# Son_of_Dark_Power.net
KiCad netlist of a schematic drawn in EAGLE
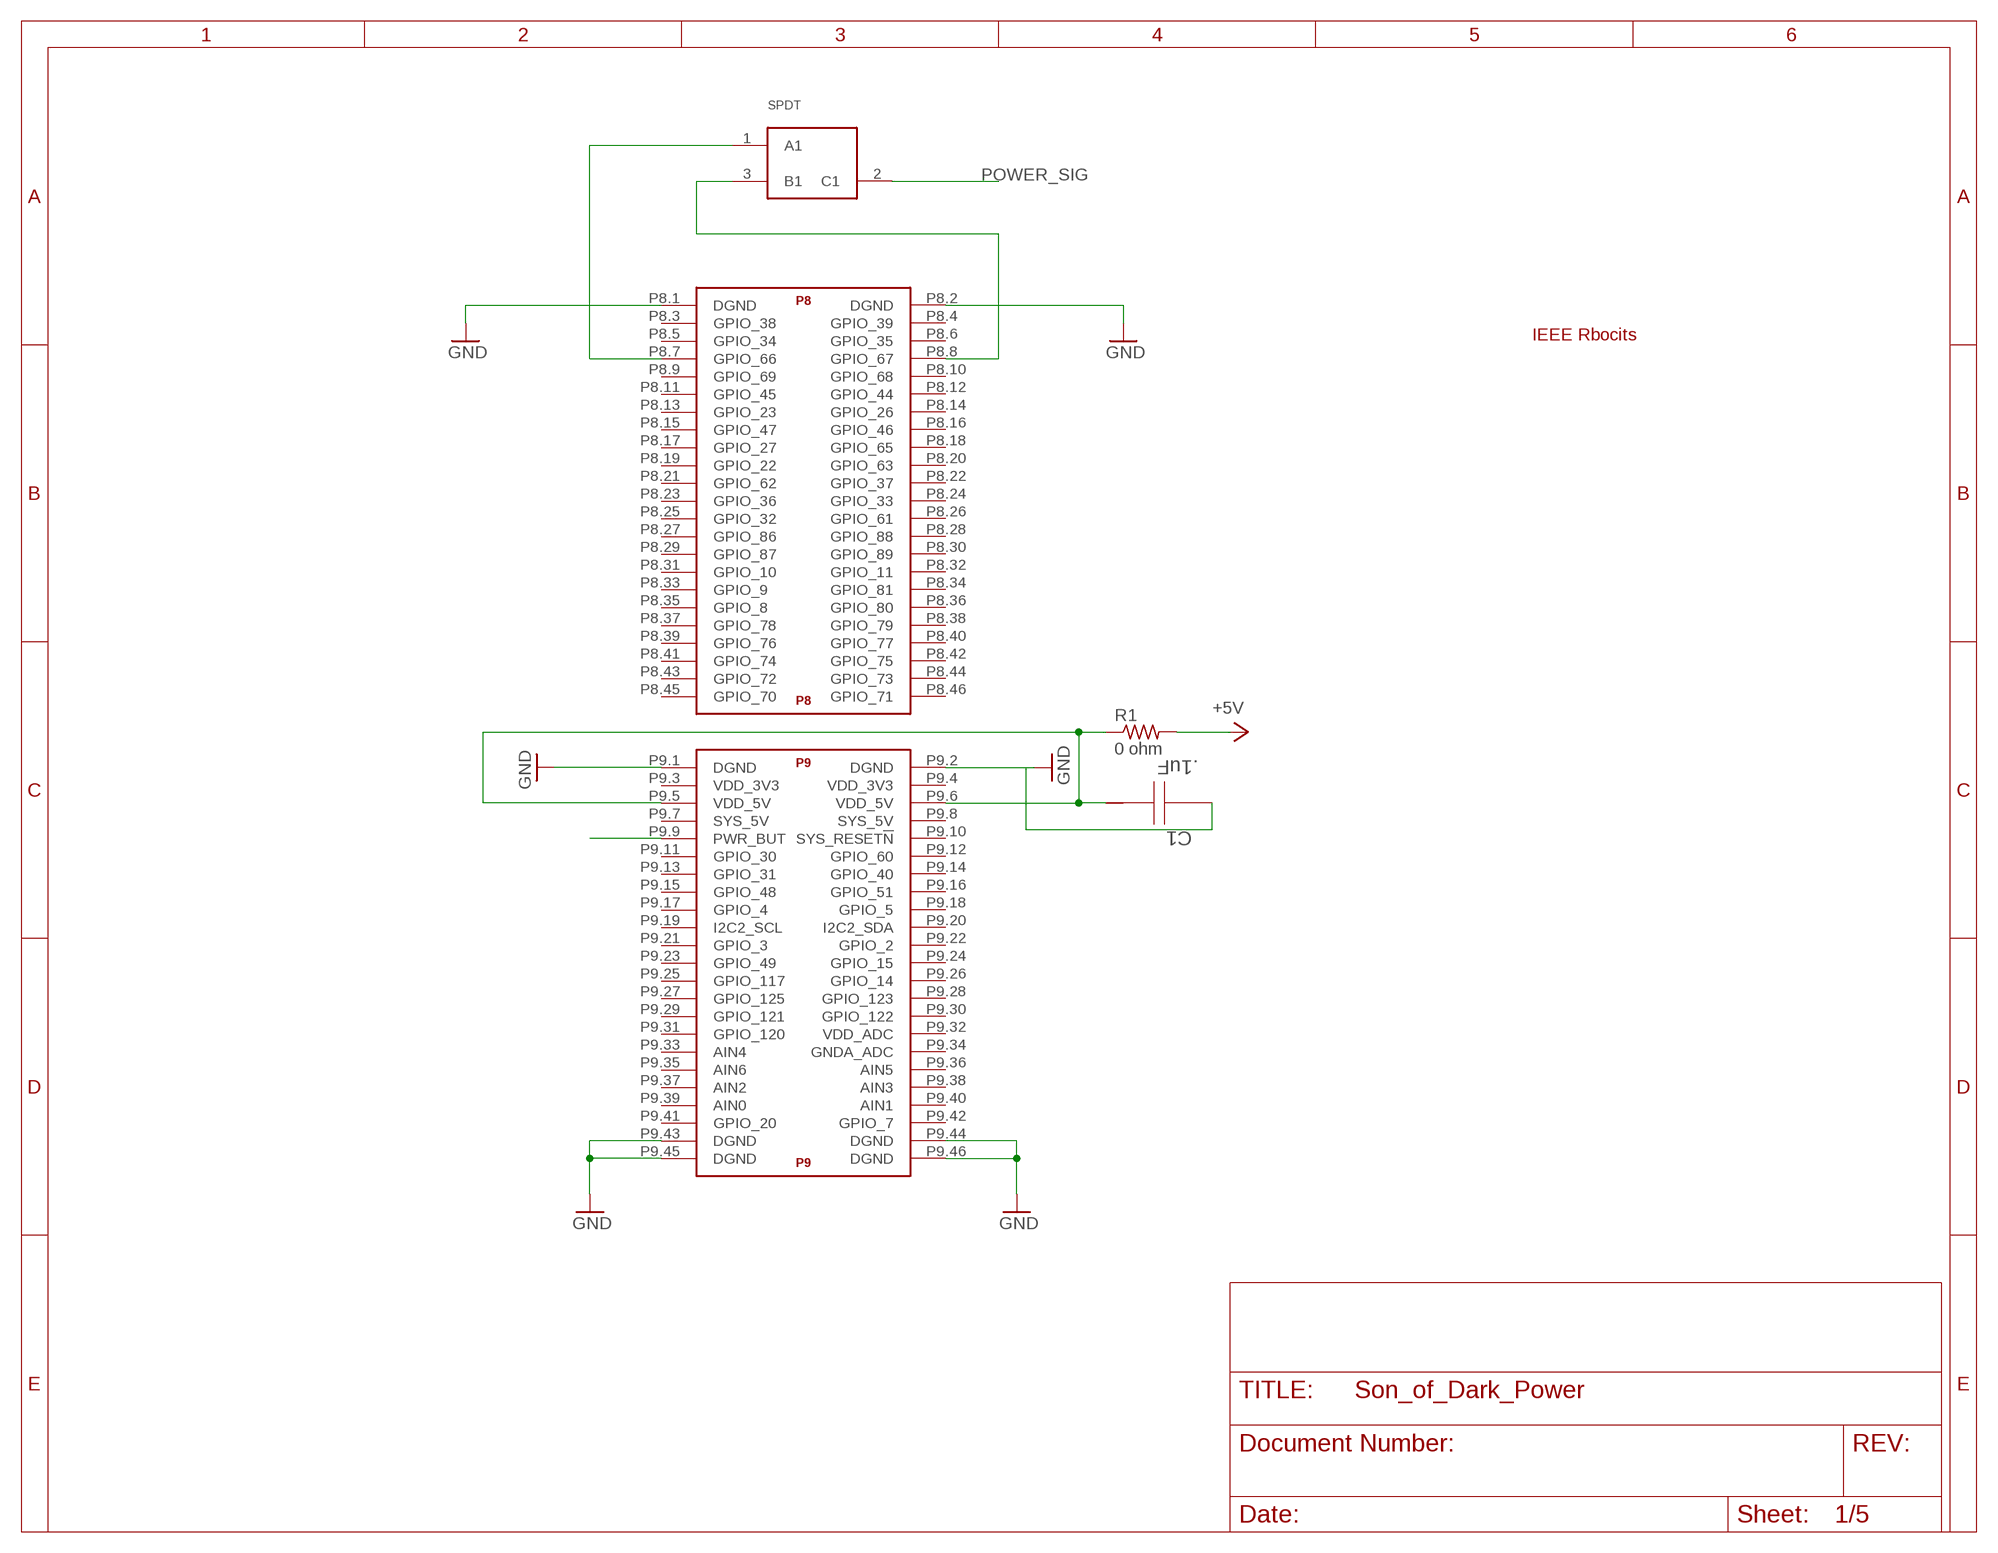
[diagram p0: schematic, sheet 1]
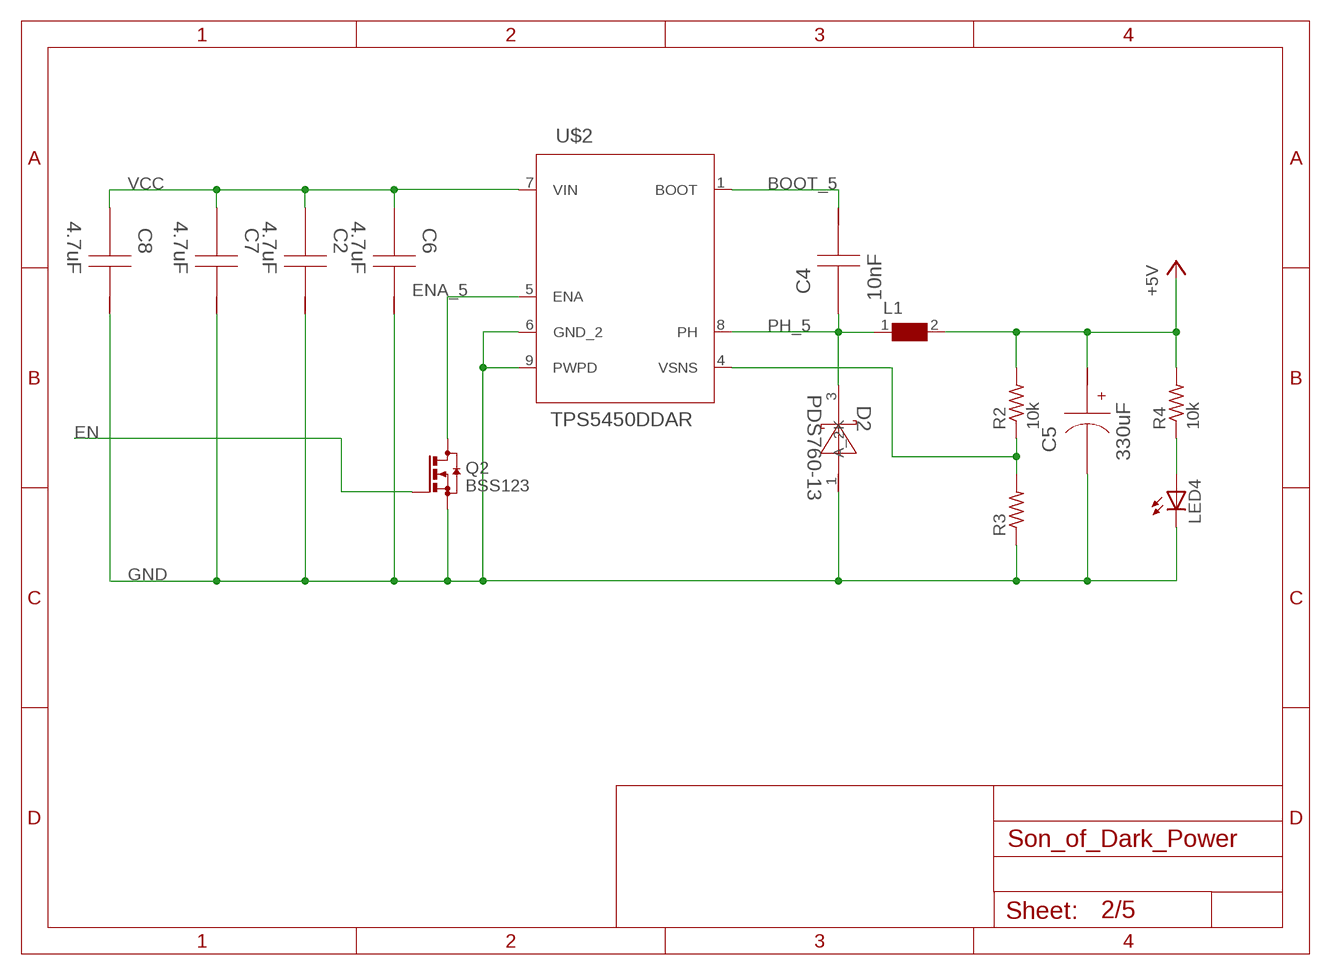
[diagram p1: schematic, sheet 2]
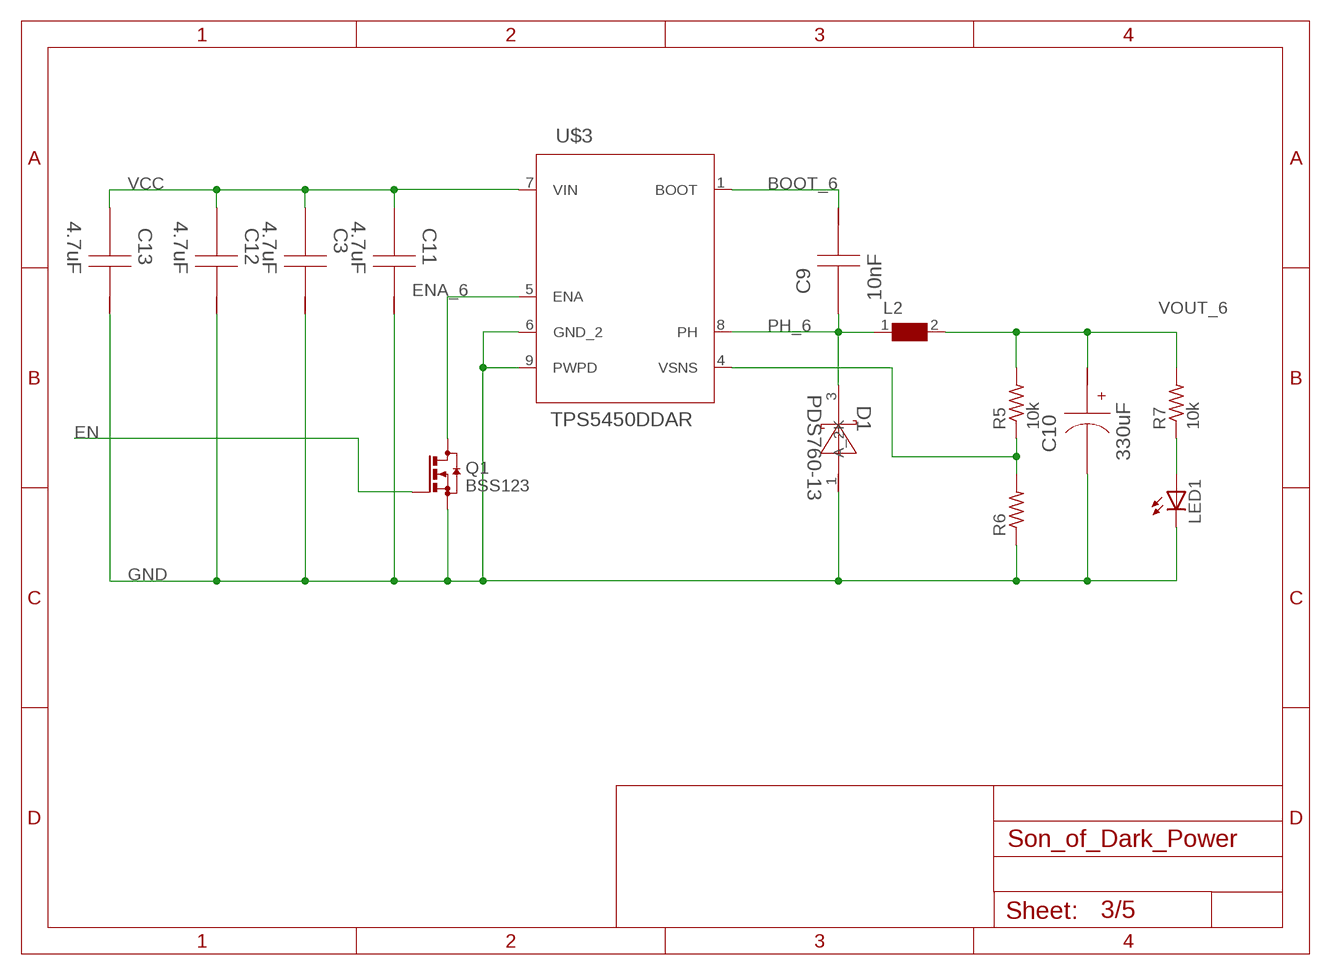
[diagram p2: schematic, sheet 3]
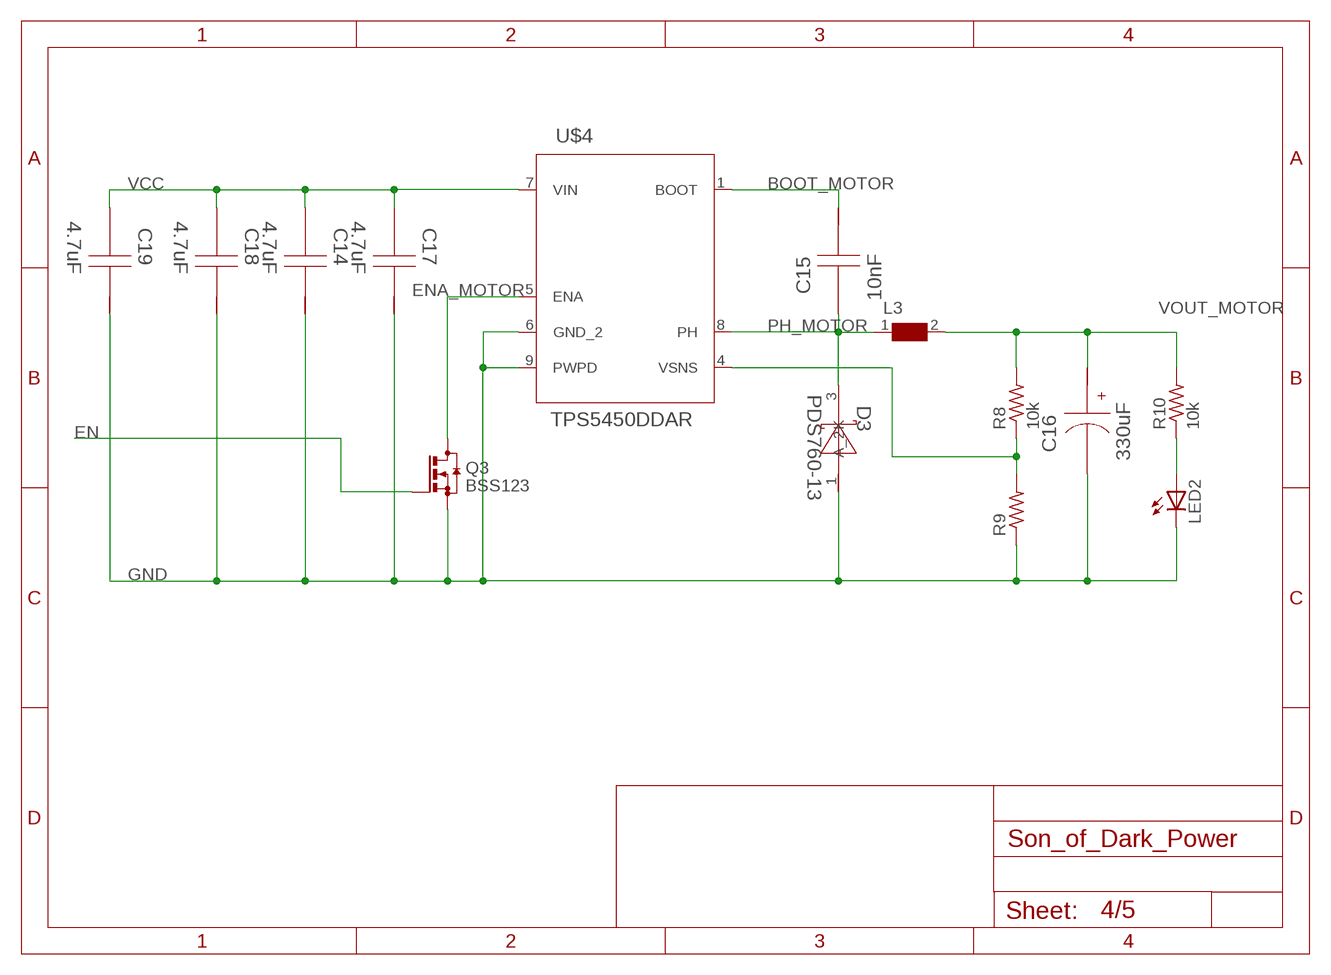
[diagram p3: schematic, sheet 4]
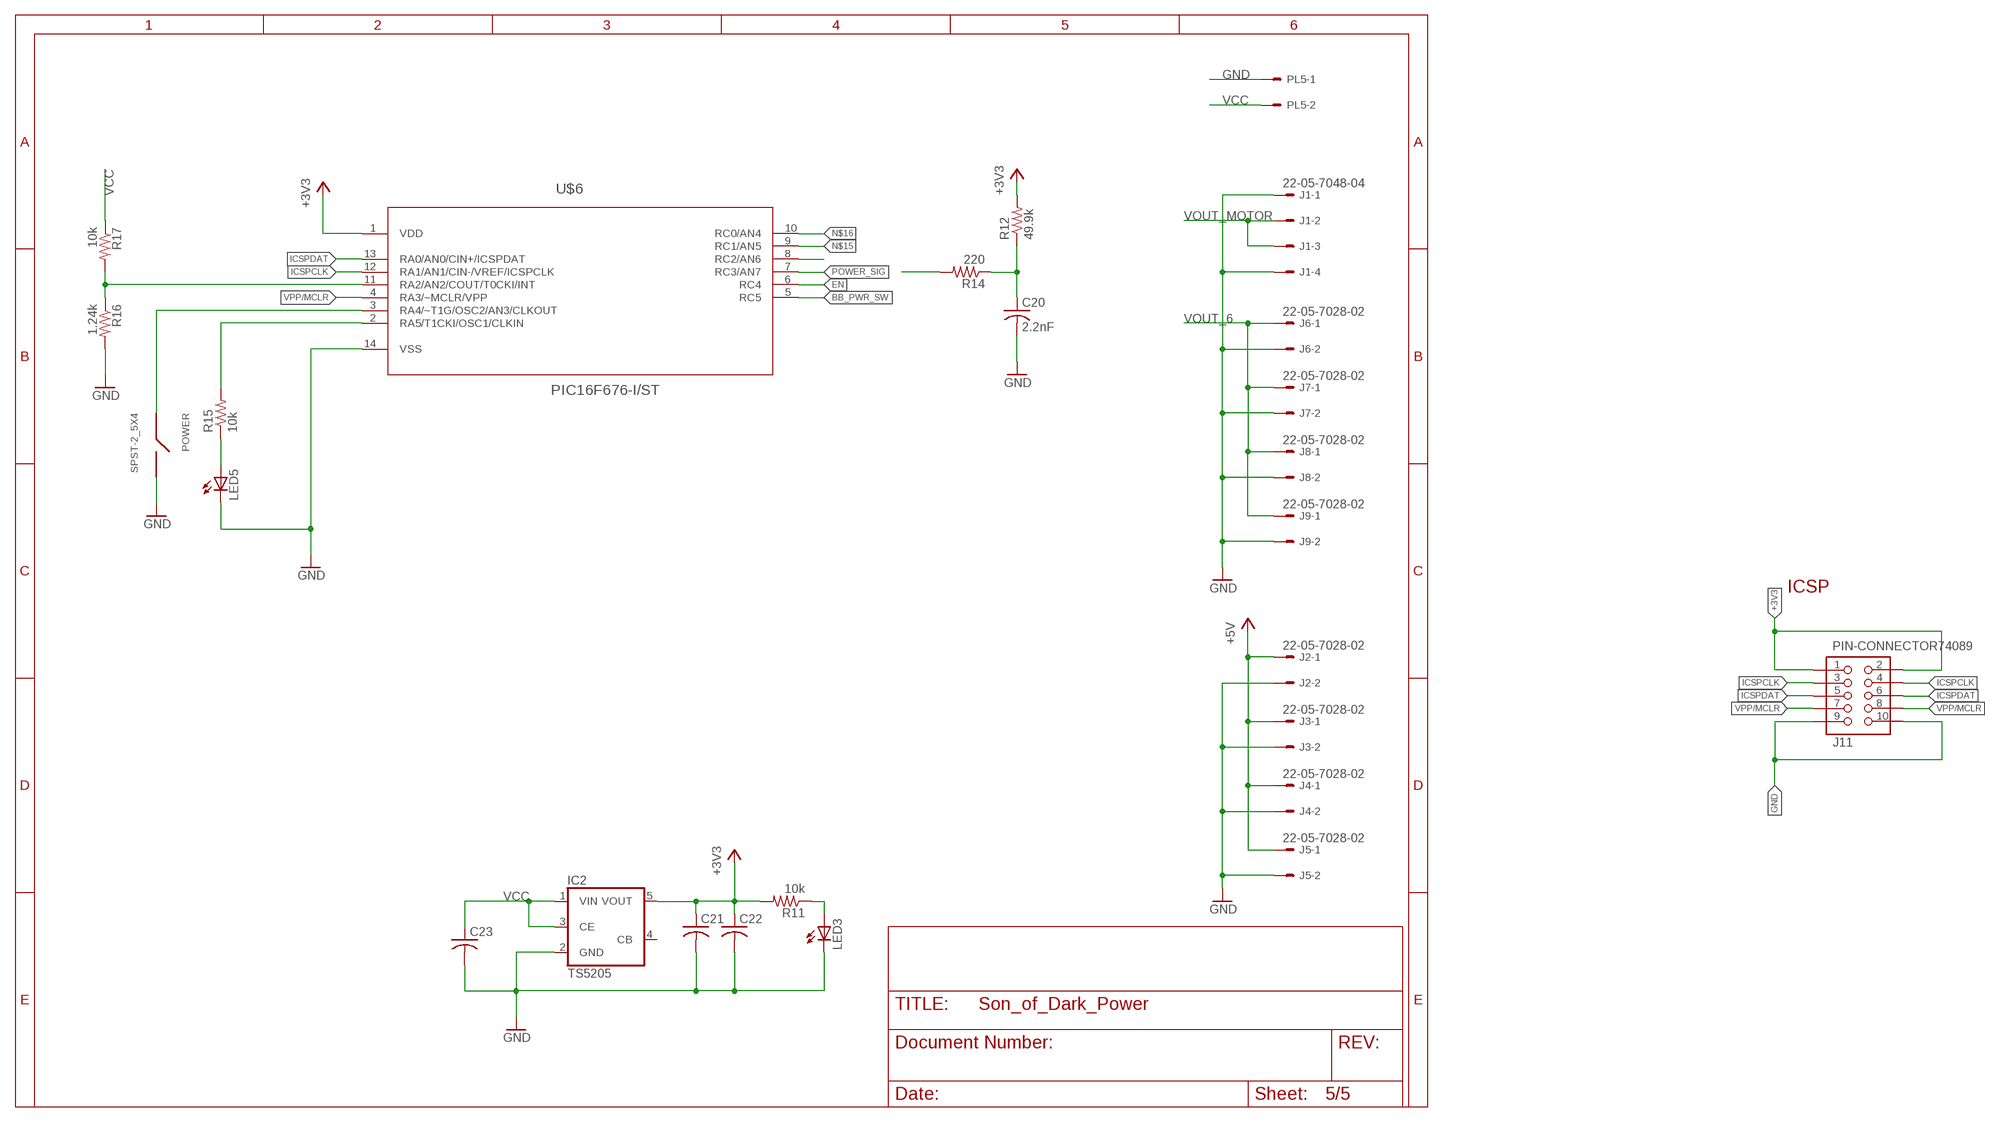
[diagram p4: schematic, sheet 5]

(export (version "E")
  (design (tool "Eeschema 10.0.6"))
  (components
    (comp (ref "C14")
      (value "4.7uF")
      (footprint "eagle-import:1206")
      (fields (field (name "MANUFACTURER_PART_NUMBER") "GRM31CR71H475KA12L"))
      (libsource (lib "eagle-import") (part "GRM31CR71H475KA12L"))
    )
    (comp (ref "C15")
      (value "10nF")
      (footprint "eagle-import:0805")
      (fields (field (name "MANUFACTURER_PART_NUMBER") "C0805C103K5RACTU"))
      (libsource (lib "eagle-import") (part "C0805C103K5RACTU"))
    )
    (comp (ref "C16")
      (value "330uF")
      (footprint "eagle-import:SM_RADIAL_10AMM")
      (fields (field (name "MANUFACTURER_PART_NUMBER") "10SVP330MX"))
      (libsource (lib "eagle-import") (part "10SVP330MX"))
    )
    (comp (ref "C17")
      (value "4.7uF")
      (footprint "eagle-import:1206")
      (fields (field (name "MANUFACTURER_PART_NUMBER") "GRM31CR71H475KA12L"))
      (libsource (lib "eagle-import") (part "GRM31CR71H475KA12L"))
    )
    (comp (ref "C18")
      (value "4.7uF")
      (footprint "eagle-import:1206")
      (fields (field (name "MANUFACTURER_PART_NUMBER") "GRM31CR71H475KA12L"))
      (libsource (lib "eagle-import") (part "GRM31CR71H475KA12L"))
    )
    (comp (ref "C19")
      (value "4.7uF")
      (footprint "eagle-import:1206")
      (fields (field (name "MANUFACTURER_PART_NUMBER") "GRM31CR71H475KA12L"))
      (libsource (lib "eagle-import") (part "GRM31CR71H475KA12L"))
    )
    (comp (ref "D3")
      (value "PDS760-13")
      (footprint "eagle-import:POWERDI5")
      (libsource (lib "eagle-import") (part "PDS760-13"))
    )
    (comp (ref "L3")
      (value "WE-HCC-7443331000_1090")
      (footprint "eagle-import:WE-HCC_1090")
      (fields (field (name "MPN") "7443331000"))
      (libsource (lib "eagle-import") (part "WE-HCC_1090-7443331000"))
    )
    (comp (ref "LED2")
      (value "LEDSML1206")
      (footprint "eagle-import:SML1206")
      (libsource (lib "eagle-import") (part "LEDSML1206"))
    )
    (comp (ref "Q3")
      (value "BSS123")
      (footprint "eagle-import:SOT23")
      (libsource (lib "eagle-import") (part "BSS123"))
    )
    (comp (ref "R8")
      (value "10k")
      (footprint "eagle-import:R1206")
      (libsource (lib "eagle-import") (part "R-US_R1206"))
    )
    (comp (ref "R9")
      (value "R-US_R1206")
      (footprint "eagle-import:R1206")
      (libsource (lib "eagle-import") (part "R-US_R1206"))
    )
    (comp (ref "R10")
      (value "10k")
      (footprint "eagle-import:R1206")
      (libsource (lib "eagle-import") (part "R-US_R1206"))
    )
    (comp (ref "U$4")
      (value "TPS5450DDAR")
      (footprint "eagle-import:R-PDSO-G8")
      (fields (field (name "MANUFACTURER_PART_NUMBER") "TPS5450DDA"))
      (libsource (lib "eagle-import") (part "TPS5450DDAR"))
    )
    (comp (ref "C20")
      (value "2.2nF")
      (footprint "eagle-import:C0603")
      (libsource (lib "eagle-import") (part "C-USC0603"))
    )
    (comp (ref "C21")
      (value "C-USC0603")
      (footprint "eagle-import:C0603")
      (libsource (lib "eagle-import") (part "C-USC0603"))
    )
    (comp (ref "C22")
      (value "C-USC0603")
      (footprint "eagle-import:C0603")
      (libsource (lib "eagle-import") (part "C-USC0603"))
    )
    (comp (ref "C23")
      (value "C-USC0603")
      (footprint "eagle-import:C0603")
      (libsource (lib "eagle-import") (part "C-USC0603"))
    )
    (comp (ref "IC2")
      (value "TS5205")
      (footprint "eagle-import:SOT25")
      (libsource (lib "eagle-import") (part "TS5205"))
    )
    (comp (ref "J1")
      (value "22-05-7048-04")
      (footprint "eagle-import:7395-04")
      (libsource (lib "eagle-import") (part "22-?-0405-7048"))
    )
    (comp (ref "J2")
      (value "22-05-7028-02")
      (footprint "eagle-import:7395-02")
      (libsource (lib "eagle-import") (part "22-?-0205-7028"))
    )
    (comp (ref "J3")
      (value "22-05-7028-02")
      (footprint "eagle-import:7395-02")
      (libsource (lib "eagle-import") (part "22-?-0205-7028"))
    )
    (comp (ref "J4")
      (value "22-05-7028-02")
      (footprint "eagle-import:7395-02")
      (libsource (lib "eagle-import") (part "22-?-0205-7028"))
    )
    (comp (ref "J5")
      (value "22-05-7028-02")
      (footprint "eagle-import:7395-02")
      (libsource (lib "eagle-import") (part "22-?-0205-7028"))
    )
    (comp (ref "J6")
      (value "22-05-7028-02")
      (footprint "eagle-import:7395-02")
      (libsource (lib "eagle-import") (part "22-?-0205-7028"))
    )
    (comp (ref "J7")
      (value "22-05-7028-02")
      (footprint "eagle-import:7395-02")
      (libsource (lib "eagle-import") (part "22-?-0205-7028"))
    )
    (comp (ref "J8")
      (value "22-05-7028-02")
      (footprint "eagle-import:7395-02")
      (libsource (lib "eagle-import") (part "22-?-0205-7028"))
    )
    (comp (ref "J9")
      (value "22-05-7028-02")
      (footprint "eagle-import:7395-02")
      (libsource (lib "eagle-import") (part "22-?-0205-7028"))
    )
    (comp (ref "J11")
      (value "PIN-CONNECTOR74089")
      (footprint "eagle-import:10-PIN-SMD")
      (libsource (lib "eagle-import") (part "PIN-CONNECTOR74089"))
    )
    (comp (ref "LED3")
      (value "LEDSML1206")
      (footprint "eagle-import:SML1206")
      (libsource (lib "eagle-import") (part "LEDSML1206"))
    )
    (comp (ref "LED5")
      (value "LEDSML1206")
      (footprint "eagle-import:SML1206")
      (libsource (lib "eagle-import") (part "LEDSML1206"))
    )
    (comp (ref "PL5")
      (value "555X-2H")
      (footprint "eagle-import:5569-2")
      (libsource (lib "eagle-import") (part "555X-2H"))
    )
    (comp (ref "POWER")
      (value "SPST-2_5X4")
      (footprint "eagle-import:SPST-TAC-4X2_5MM")
      (libsource (lib "eagle-import") (part "SPST-2_5X4"))
    )
    (comp (ref "R11")
      (value "10k")
      (footprint "eagle-import:R1206")
      (libsource (lib "eagle-import") (part "R-US_R1206"))
    )
    (comp (ref "R12")
      (value "49.9k")
      (footprint "eagle-import:R0603")
      (libsource (lib "eagle-import") (part "R-US_R0603"))
    )
    (comp (ref "R14")
      (value "220")
      (footprint "eagle-import:R0603")
      (libsource (lib "eagle-import") (part "R-US_R0603"))
    )
    (comp (ref "R15")
      (value "10k")
      (footprint "eagle-import:R1206")
      (libsource (lib "eagle-import") (part "R-US_R1206"))
    )
    (comp (ref "R16")
      (value "1.24k")
      (footprint "eagle-import:R0603")
      (libsource (lib "eagle-import") (part "R-US_R0603"))
    )
    (comp (ref "R17")
      (value "10k")
      (footprint "eagle-import:R0603")
      (libsource (lib "eagle-import") (part "R-US_R0603"))
    )
    (comp (ref "U$6")
      (value "PIC16F676-I/ST")
      (footprint "eagle-import:SOP65P640X120-14N")
      (libsource (lib "eagle-import") (part "PIC16F676-I/ST"))
    )
    (comp (ref "C1")
      (value ".1uF")
      (footprint "eagle-import:1206")
      (fields (field (name "MANUFACTURER_PART_NUMBER") "C3216X5R1A106K"))
      (libsource (lib "eagle-import") (part "C3216X5R1A106K"))
    )
    (comp (ref "R1")
      (value "0 ohm")
      (footprint "eagle-import:R1206")
      (libsource (lib "eagle-import") (part "R-US_R1206"))
    )
    (comp (ref "SPDT")
      (value "SPDT_SWITCH")
      (footprint "eagle-import:SPDT")
      (libsource (lib "eagle-import") (part "SPDT_SWITCH"))
    )
    (comp (ref "U$1")
      (value "BEAGLE_BONE_BLACK_CAPE")
      (footprint "eagle-import:BEAGLE_BONE_BLACK_CAPE")
      (libsource (lib "eagle-import") (part "BEAGLE_BONE_BLACK_CAPE"))
    )
    (comp (ref "U$5")
      (value "LOGO-IEEE")
      (footprint "eagle-import:LOGO")
      (libsource (lib "eagle-import") (part "LOGO-IEEE"))
    )
    (comp (ref "C3")
      (value "4.7uF")
      (footprint "eagle-import:1206")
      (fields (field (name "MANUFACTURER_PART_NUMBER") "GRM31CR71H475KA12L"))
      (libsource (lib "eagle-import") (part "GRM31CR71H475KA12L"))
    )
    (comp (ref "C9")
      (value "10nF")
      (footprint "eagle-import:0805")
      (fields (field (name "MANUFACTURER_PART_NUMBER") "C0805C103K5RACTU"))
      (libsource (lib "eagle-import") (part "C0805C103K5RACTU"))
    )
    (comp (ref "C10")
      (value "330uF")
      (footprint "eagle-import:SM_RADIAL_10AMM")
      (fields (field (name "MANUFACTURER_PART_NUMBER") "10SVP330MX"))
      (libsource (lib "eagle-import") (part "10SVP330MX"))
    )
    (comp (ref "C11")
      (value "4.7uF")
      (footprint "eagle-import:1206")
      (fields (field (name "MANUFACTURER_PART_NUMBER") "GRM31CR71H475KA12L"))
      (libsource (lib "eagle-import") (part "GRM31CR71H475KA12L"))
    )
    (comp (ref "C12")
      (value "4.7uF")
      (footprint "eagle-import:1206")
      (fields (field (name "MANUFACTURER_PART_NUMBER") "GRM31CR71H475KA12L"))
      (libsource (lib "eagle-import") (part "GRM31CR71H475KA12L"))
    )
    (comp (ref "C13")
      (value "4.7uF")
      (footprint "eagle-import:1206")
      (fields (field (name "MANUFACTURER_PART_NUMBER") "GRM31CR71H475KA12L"))
      (libsource (lib "eagle-import") (part "GRM31CR71H475KA12L"))
    )
    (comp (ref "D1")
      (value "PDS760-13")
      (footprint "eagle-import:POWERDI5")
      (libsource (lib "eagle-import") (part "PDS760-13"))
    )
    (comp (ref "L2")
      (value "WE-HCC-7443331000_1090")
      (footprint "eagle-import:WE-HCC_1090")
      (fields (field (name "MPN") "7443331000"))
      (libsource (lib "eagle-import") (part "WE-HCC_1090-7443331000"))
    )
    (comp (ref "LED1")
      (value "LEDSML1206")
      (footprint "eagle-import:SML1206")
      (libsource (lib "eagle-import") (part "LEDSML1206"))
    )
    (comp (ref "Q1")
      (value "BSS123")
      (footprint "eagle-import:SOT23")
      (libsource (lib "eagle-import") (part "BSS123"))
    )
    (comp (ref "R5")
      (value "10k")
      (footprint "eagle-import:R1206")
      (libsource (lib "eagle-import") (part "R-US_R1206"))
    )
    (comp (ref "R6")
      (value "R-US_R1206")
      (footprint "eagle-import:R1206")
      (libsource (lib "eagle-import") (part "R-US_R1206"))
    )
    (comp (ref "R7")
      (value "10k")
      (footprint "eagle-import:R1206")
      (libsource (lib "eagle-import") (part "R-US_R1206"))
    )
    (comp (ref "U$3")
      (value "TPS5450DDAR")
      (footprint "eagle-import:R-PDSO-G8")
      (fields (field (name "MANUFACTURER_PART_NUMBER") "TPS5450DDA"))
      (libsource (lib "eagle-import") (part "TPS5450DDAR"))
    )
    (comp (ref "C2")
      (value "4.7uF")
      (footprint "eagle-import:1206")
      (fields (field (name "MANUFACTURER_PART_NUMBER") "GRM31CR71H475KA12L"))
      (libsource (lib "eagle-import") (part "GRM31CR71H475KA12L"))
    )
    (comp (ref "C4")
      (value "10nF")
      (footprint "eagle-import:0805")
      (fields (field (name "MANUFACTURER_PART_NUMBER") "C0805C103K5RACTU"))
      (libsource (lib "eagle-import") (part "C0805C103K5RACTU"))
    )
    (comp (ref "C5")
      (value "330uF")
      (footprint "eagle-import:SM_RADIAL_10AMM")
      (fields (field (name "MANUFACTURER_PART_NUMBER") "10SVP330MX"))
      (libsource (lib "eagle-import") (part "10SVP330MX"))
    )
    (comp (ref "C6")
      (value "4.7uF")
      (footprint "eagle-import:1206")
      (fields (field (name "MANUFACTURER_PART_NUMBER") "GRM31CR71H475KA12L"))
      (libsource (lib "eagle-import") (part "GRM31CR71H475KA12L"))
    )
    (comp (ref "C7")
      (value "4.7uF")
      (footprint "eagle-import:1206")
      (fields (field (name "MANUFACTURER_PART_NUMBER") "GRM31CR71H475KA12L"))
      (libsource (lib "eagle-import") (part "GRM31CR71H475KA12L"))
    )
    (comp (ref "C8")
      (value "4.7uF")
      (footprint "eagle-import:1206")
      (fields (field (name "MANUFACTURER_PART_NUMBER") "GRM31CR71H475KA12L"))
      (libsource (lib "eagle-import") (part "GRM31CR71H475KA12L"))
    )
    (comp (ref "D2")
      (value "PDS760-13")
      (footprint "eagle-import:POWERDI5")
      (libsource (lib "eagle-import") (part "PDS760-13"))
    )
    (comp (ref "L1")
      (value "WE-HCC-7443331000_1090")
      (footprint "eagle-import:WE-HCC_1090")
      (fields (field (name "MPN") "7443331000"))
      (libsource (lib "eagle-import") (part "WE-HCC_1090-7443331000"))
    )
    (comp (ref "LED4")
      (value "LEDSML1206")
      (footprint "eagle-import:SML1206")
      (libsource (lib "eagle-import") (part "LEDSML1206"))
    )
    (comp (ref "Q2")
      (value "BSS123")
      (footprint "eagle-import:SOT23")
      (libsource (lib "eagle-import") (part "BSS123"))
    )
    (comp (ref "R2")
      (value "10k")
      (footprint "eagle-import:R1206")
      (libsource (lib "eagle-import") (part "R-US_R1206"))
    )
    (comp (ref "R3")
      (value "R-US_R1206")
      (footprint "eagle-import:R1206")
      (libsource (lib "eagle-import") (part "R-US_R1206"))
    )
    (comp (ref "R4")
      (value "10k")
      (footprint "eagle-import:R1206")
      (libsource (lib "eagle-import") (part "R-US_R1206"))
    )
    (comp (ref "U$2")
      (value "TPS5450DDAR")
      (footprint "eagle-import:R-PDSO-G8")
      (fields (field (name "MANUFACTURER_PART_NUMBER") "TPS5450DDA"))
      (libsource (lib "eagle-import") (part "TPS5450DDAR"))
    )
  )
  (nets
    (net (code "1") (name "+3V3") (class "Default")
      (node (ref "C21") (pin "1") (pinfunction "1_1") (pintype "passive"))
      (node (ref "C22") (pin "1") (pinfunction "1_1") (pintype "passive"))
      (node (ref "IC2") (pin "5") (pinfunction "VOUT_5") (pintype "passive"))
      (node (ref "J11") (pin "1") (pinfunction "P$1_1") (pintype "power_in"))
      (node (ref "J11") (pin "2") (pinfunction "P$2_2") (pintype "power_in"))
      (node (ref "R11") (pin "2") (pinfunction "2_2") (pintype "passive"))
      (node (ref "R12") (pin "2") (pinfunction "2_2") (pintype "passive"))
      (node (ref "U$6") (pin "1") (pinfunction "VDD_1") (pintype "power_in"))
    )
    (net (code "2") (name "+5V") (class "Default")
      (node (ref "C5") (pin "1") (pinfunction "+_1") (pintype "passive"))
      (node (ref "J2") (pin "1") (pinfunction "S_1") (pintype "passive"))
      (node (ref "J3") (pin "1") (pinfunction "S_1") (pintype "passive"))
      (node (ref "J4") (pin "1") (pinfunction "S_1") (pintype "passive"))
      (node (ref "J5") (pin "1") (pinfunction "S_1") (pintype "passive"))
      (node (ref "L1") (pin "2") (pinfunction "2_2") (pintype "passive"))
      (node (ref "R1") (pin "2") (pinfunction "2_2") (pintype "passive"))
      (node (ref "R2") (pin "2") (pinfunction "2_2") (pintype "passive"))
      (node (ref "R4") (pin "2") (pinfunction "2_2") (pintype "passive"))
    )
    (net (code "3") (name "BB_PWR_SW") (class "Default")
      (node (ref "U$1") (pin "P9.9") (pinfunction "PWR_BUT_P9.9") (pintype "bidirectional"))
      (node (ref "U$6") (pin "5") (pinfunction "RC5_5") (pintype "bidirectional"))
    )
    (net (code "4") (name "BOOT_5") (class "Default")
      (node (ref "C4") (pin "1") (pinfunction "1_1") (pintype "passive"))
      (node (ref "U$2") (pin "1") (pinfunction "BOOT_1") (pintype "passive"))
    )
    (net (code "5") (name "BOOT_6") (class "Default")
      (node (ref "C9") (pin "1") (pinfunction "1_1") (pintype "passive"))
      (node (ref "U$3") (pin "1") (pinfunction "BOOT_1") (pintype "passive"))
    )
    (net (code "6") (name "BOOT_MOTOR") (class "Default")
      (node (ref "C15") (pin "1") (pinfunction "1_1") (pintype "passive"))
      (node (ref "U$4") (pin "1") (pinfunction "BOOT_1") (pintype "passive"))
    )
    (net (code "7") (name "EN") (class "Default")
      (node (ref "Q1") (pin "1") (pinfunction "G_1") (pintype "passive"))
      (node (ref "Q2") (pin "1") (pinfunction "G_1") (pintype "passive"))
      (node (ref "Q3") (pin "1") (pinfunction "G_1") (pintype "passive"))
      (node (ref "U$6") (pin "6") (pinfunction "RC4_6") (pintype "bidirectional"))
    )
    (net (code "8") (name "ENA_5") (class "Default")
      (node (ref "Q2") (pin "3") (pinfunction "D_3") (pintype "passive"))
      (node (ref "U$2") (pin "5") (pinfunction "ENA_5") (pintype "passive"))
    )
    (net (code "9") (name "ENA_6") (class "Default")
      (node (ref "Q1") (pin "3") (pinfunction "D_3") (pintype "passive"))
      (node (ref "U$3") (pin "5") (pinfunction "ENA_5") (pintype "passive"))
    )
    (net (code "10") (name "ENA_MOTOR") (class "Default")
      (node (ref "Q3") (pin "3") (pinfunction "D_3") (pintype "passive"))
      (node (ref "U$4") (pin "5") (pinfunction "ENA_5") (pintype "passive"))
    )
    (net (code "11") (name "GND") (class "Default")
      (node (ref "C1") (pin "2") (pinfunction "2_2") (pintype "passive"))
      (node (ref "C10") (pin "2") (pinfunction "-_2") (pintype "passive"))
      (node (ref "C11") (pin "1") (pinfunction "1_1") (pintype "passive"))
      (node (ref "C12") (pin "1") (pinfunction "1_1") (pintype "passive"))
      (node (ref "C13") (pin "1") (pinfunction "1_1") (pintype "passive"))
      (node (ref "C14") (pin "1") (pinfunction "1_1") (pintype "passive"))
      (node (ref "C16") (pin "2") (pinfunction "-_2") (pintype "passive"))
      (node (ref "C17") (pin "1") (pinfunction "1_1") (pintype "passive"))
      (node (ref "C18") (pin "1") (pinfunction "1_1") (pintype "passive"))
      (node (ref "C19") (pin "1") (pinfunction "1_1") (pintype "passive"))
      (node (ref "C2") (pin "1") (pinfunction "1_1") (pintype "passive"))
      (node (ref "C20") (pin "2") (pinfunction "2_2") (pintype "passive"))
      (node (ref "C21") (pin "2") (pinfunction "2_2") (pintype "passive"))
      (node (ref "C22") (pin "2") (pinfunction "2_2") (pintype "passive"))
      (node (ref "C23") (pin "2") (pinfunction "2_2") (pintype "passive"))
      (node (ref "C3") (pin "1") (pinfunction "1_1") (pintype "passive"))
      (node (ref "C5") (pin "2") (pinfunction "-_2") (pintype "passive"))
      (node (ref "C6") (pin "1") (pinfunction "1_1") (pintype "passive"))
      (node (ref "C7") (pin "1") (pinfunction "1_1") (pintype "passive"))
      (node (ref "C8") (pin "1") (pinfunction "1_1") (pintype "passive"))
      (node (ref "D1") (pin "1") (pinfunction "A_2_1") (pintype "passive"))
      (node (ref "D2") (pin "1") (pinfunction "A_2_1") (pintype "passive"))
      (node (ref "D3") (pin "1") (pinfunction "A_2_1") (pintype "passive"))
      (node (ref "IC2") (pin "2") (pinfunction "GND_2") (pintype "passive"))
      (node (ref "J1") (pin "1") (pinfunction "S_1") (pintype "passive"))
      (node (ref "J1") (pin "4") (pinfunction "S_4") (pintype "passive"))
      (node (ref "J11") (pin "10") (pinfunction "P$10_10") (pintype "power_in"))
      (node (ref "J11") (pin "9") (pinfunction "P$9_9") (pintype "power_in"))
      (node (ref "J2") (pin "2") (pinfunction "S_2") (pintype "passive"))
      (node (ref "J3") (pin "2") (pinfunction "S_2") (pintype "passive"))
      (node (ref "J4") (pin "2") (pinfunction "S_2") (pintype "passive"))
      (node (ref "J5") (pin "2") (pinfunction "S_2") (pintype "passive"))
      (node (ref "J6") (pin "2") (pinfunction "S_2") (pintype "passive"))
      (node (ref "J7") (pin "2") (pinfunction "S_2") (pintype "passive"))
      (node (ref "J8") (pin "2") (pinfunction "S_2") (pintype "passive"))
      (node (ref "J9") (pin "2") (pinfunction "S_2") (pintype "passive"))
      (node (ref "LED1") (pin "C") (pinfunction "C_C") (pintype "passive"))
      (node (ref "LED2") (pin "C") (pinfunction "C_C") (pintype "passive"))
      (node (ref "LED3") (pin "C") (pinfunction "C_C") (pintype "passive"))
      (node (ref "LED4") (pin "C") (pinfunction "C_C") (pintype "passive"))
      (node (ref "LED5") (pin "C") (pinfunction "C_C") (pintype "passive"))
      (node (ref "PL5") (pin "1") (pinfunction "S_1") (pintype "passive"))
      (node (ref "POWER") (pin "P$2") (pinfunction "P$2_P$2") (pintype "bidirectional"))
      (node (ref "Q1") (pin "2") (pinfunction "S_2") (pintype "passive"))
      (node (ref "Q2") (pin "2") (pinfunction "S_2") (pintype "passive"))
      (node (ref "Q3") (pin "2") (pinfunction "S_2") (pintype "passive"))
      (node (ref "R16") (pin "2") (pinfunction "2_2") (pintype "passive"))
      (node (ref "R3") (pin "1") (pinfunction "1_1") (pintype "passive"))
      (node (ref "R6") (pin "1") (pinfunction "1_1") (pintype "passive"))
      (node (ref "R9") (pin "1") (pinfunction "1_1") (pintype "passive"))
      (node (ref "U$1") (pin "P8.1") (pinfunction "DGND_P8.1") (pintype "bidirectional"))
      (node (ref "U$1") (pin "P8.2") (pinfunction "DGND_P8.2") (pintype "bidirectional"))
      (node (ref "U$1") (pin "P9.1") (pinfunction "DGND_P9.1") (pintype "bidirectional"))
      (node (ref "U$1") (pin "P9.2") (pinfunction "DGND_P9.2") (pintype "bidirectional"))
      (node (ref "U$1") (pin "P9.43") (pinfunction "DGND_P9.43") (pintype "bidirectional"))
      (node (ref "U$1") (pin "P9.44") (pinfunction "DGND_P9.44") (pintype "bidirectional"))
      (node (ref "U$1") (pin "P9.45") (pinfunction "DGND_P9.45") (pintype "bidirectional"))
      (node (ref "U$1") (pin "P9.46") (pinfunction "DGND_P9.46") (pintype "bidirectional"))
      (node (ref "U$2") (pin "6") (pinfunction "GND_2_6") (pintype "passive"))
      (node (ref "U$2") (pin "9") (pinfunction "PWPD_9") (pintype "passive"))
      (node (ref "U$3") (pin "6") (pinfunction "GND_2_6") (pintype "passive"))
      (node (ref "U$3") (pin "9") (pinfunction "PWPD_9") (pintype "passive"))
      (node (ref "U$4") (pin "6") (pinfunction "GND_2_6") (pintype "passive"))
      (node (ref "U$4") (pin "9") (pinfunction "PWPD_9") (pintype "passive"))
      (node (ref "U$6") (pin "14") (pinfunction "VSS_14") (pintype "power_in"))
    )
    (net (code "12") (name "ICSPCLK") (class "Default")
      (node (ref "J11") (pin "3") (pinfunction "P$3_3") (pintype "power_in"))
      (node (ref "J11") (pin "4") (pinfunction "P$4_4") (pintype "power_in"))
      (node (ref "U$6") (pin "12") (pinfunction "RA1/AN1/CIN-/VREF/ICSPCLK_12") (pintype "bidirectional"))
    )
    (net (code "13") (name "ICSPDAT") (class "Default")
      (node (ref "J11") (pin "5") (pinfunction "P$5_5") (pintype "power_in"))
      (node (ref "J11") (pin "6") (pinfunction "P$6_6") (pintype "power_in"))
      (node (ref "U$6") (pin "13") (pinfunction "RA0/AN0/CIN+/ICSPDAT_13") (pintype "bidirectional"))
    )
    (net (code "14") (name "N$15") (class "Default")
      (node (ref "U$6") (pin "9") (pinfunction "RC1/AN5_9") (pintype "bidirectional"))
    )
    (net (code "15") (name "N$16") (class "Default")
      (node (ref "U$6") (pin "10") (pinfunction "RC0/AN4_10") (pintype "bidirectional"))
    )
    (net (code "16") (name "Net-(C1-Pad1)") (class "Default")
      (node (ref "C1") (pin "1") (pinfunction "1_1") (pintype "passive"))
      (node (ref "R1") (pin "1") (pinfunction "1_1") (pintype "passive"))
      (node (ref "U$1") (pin "P9.5") (pinfunction "VDD_5V_P9.5") (pintype "bidirectional"))
      (node (ref "U$1") (pin "P9.6") (pinfunction "VDD_5V_P9.6") (pintype "bidirectional"))
    )
    (net (code "17") (name "Net-(C20-Pad1)") (class "Default")
      (node (ref "C20") (pin "1") (pinfunction "1_1") (pintype "passive"))
      (node (ref "R12") (pin "1") (pinfunction "1_1") (pintype "passive"))
      (node (ref "R14") (pin "1") (pinfunction "1_1") (pintype "passive"))
    )
    (net (code "18") (name "Net-(LED1-PadA)") (class "Default")
      (node (ref "LED1") (pin "A") (pinfunction "A_A") (pintype "passive"))
      (node (ref "R7") (pin "1") (pinfunction "1_1") (pintype "passive"))
    )
    (net (code "19") (name "Net-(LED2-PadA)") (class "Default")
      (node (ref "LED2") (pin "A") (pinfunction "A_A") (pintype "passive"))
      (node (ref "R10") (pin "1") (pinfunction "1_1") (pintype "passive"))
    )
    (net (code "20") (name "Net-(LED3-PadA)") (class "Default")
      (node (ref "LED3") (pin "A") (pinfunction "A_A") (pintype "passive"))
      (node (ref "R11") (pin "1") (pinfunction "1_1") (pintype "passive"))
    )
    (net (code "21") (name "Net-(LED4-PadA)") (class "Default")
      (node (ref "LED4") (pin "A") (pinfunction "A_A") (pintype "passive"))
      (node (ref "R4") (pin "1") (pinfunction "1_1") (pintype "passive"))
    )
    (net (code "22") (name "Net-(LED5-PadA)") (class "Default")
      (node (ref "LED5") (pin "A") (pinfunction "A_A") (pintype "passive"))
      (node (ref "R15") (pin "1") (pinfunction "1_1") (pintype "passive"))
    )
    (net (code "23") (name "Net-(SPDT-A1)") (class "Default")
      (node (ref "SPDT") (pin "1") (pinfunction "A1_1") (pintype "bidirectional"))
      (node (ref "U$1") (pin "P8.7") (pinfunction "GPIO_66_P8.7") (pintype "bidirectional"))
    )
    (net (code "24") (name "Net-(SPDT-B1)") (class "Default")
      (node (ref "SPDT") (pin "3") (pinfunction "B1_3") (pintype "bidirectional"))
      (node (ref "U$1") (pin "P8.8") (pinfunction "GPIO_67_P8.8") (pintype "bidirectional"))
    )
    (net (code "25") (name "Net-(U$2-VSNS)") (class "Default")
      (node (ref "R2") (pin "1") (pinfunction "1_1") (pintype "passive"))
      (node (ref "R3") (pin "2") (pinfunction "2_2") (pintype "passive"))
      (node (ref "U$2") (pin "4") (pinfunction "VSNS_4") (pintype "passive"))
    )
    (net (code "26") (name "Net-(U$3-VSNS)") (class "Default")
      (node (ref "R5") (pin "1") (pinfunction "1_1") (pintype "passive"))
      (node (ref "R6") (pin "2") (pinfunction "2_2") (pintype "passive"))
      (node (ref "U$3") (pin "4") (pinfunction "VSNS_4") (pintype "passive"))
    )
    (net (code "27") (name "Net-(U$4-VSNS)") (class "Default")
      (node (ref "R8") (pin "1") (pinfunction "1_1") (pintype "passive"))
      (node (ref "R9") (pin "2") (pinfunction "2_2") (pintype "passive"))
      (node (ref "U$4") (pin "4") (pinfunction "VSNS_4") (pintype "passive"))
    )
    (net (code "28") (name "Net-(U$6-RA2{slash}AN2{slash}COUT{slash}T0CKI{slash}INT)") (class "Default")
      (node (ref "R16") (pin "1") (pinfunction "1_1") (pintype "passive"))
      (node (ref "R17") (pin "2") (pinfunction "2_2") (pintype "passive"))
      (node (ref "U$6") (pin "11") (pinfunction "RA2/AN2/COUT/T0CKI/INT_11") (pintype "bidirectional"))
    )
    (net (code "29") (name "Net-(U$6-RA4{slash}~{T1G{slash}OSC2{slash}AN3{slash}CLKOUT})") (class "Default")
      (node (ref "POWER") (pin "P$1") (pinfunction "P$1_P$1") (pintype "bidirectional"))
      (node (ref "U$6") (pin "3") (pinfunction "RA4/~{T1G/OSC2/AN3/CLKOUT}_3") (pintype "bidirectional"))
    )
    (net (code "30") (name "Net-(U$6-RA5{slash}T1CKI{slash}OSC1{slash}CLKIN)") (class "Default")
      (node (ref "R15") (pin "2") (pinfunction "2_2") (pintype "passive"))
      (node (ref "U$6") (pin "2") (pinfunction "RA5/T1CKI/OSC1/CLKIN_2") (pintype "bidirectional"))
    )
    (net (code "31") (name "PH_5") (class "Default")
      (node (ref "C4") (pin "2") (pinfunction "2_2") (pintype "passive"))
      (node (ref "D2") (pin "3") (pinfunction "K_3") (pintype "passive"))
      (node (ref "L1") (pin "1") (pinfunction "1_1") (pintype "passive"))
      (node (ref "U$2") (pin "8") (pinfunction "PH_8") (pintype "passive"))
    )
    (net (code "32") (name "PH_6") (class "Default")
      (node (ref "C9") (pin "2") (pinfunction "2_2") (pintype "passive"))
      (node (ref "D1") (pin "3") (pinfunction "K_3") (pintype "passive"))
      (node (ref "L2") (pin "1") (pinfunction "1_1") (pintype "passive"))
      (node (ref "U$3") (pin "8") (pinfunction "PH_8") (pintype "passive"))
    )
    (net (code "33") (name "PH_MOTOR") (class "Default")
      (node (ref "C15") (pin "2") (pinfunction "2_2") (pintype "passive"))
      (node (ref "D3") (pin "3") (pinfunction "K_3") (pintype "passive"))
      (node (ref "L3") (pin "1") (pinfunction "1_1") (pintype "passive"))
      (node (ref "U$4") (pin "8") (pinfunction "PH_8") (pintype "passive"))
    )
    (net (code "34") (name "POWER_SIG") (class "Default")
      (node (ref "SPDT") (pin "2") (pinfunction "C1_2") (pintype "bidirectional"))
      (node (ref "U$6") (pin "7") (pinfunction "RC3/AN7_7") (pintype "bidirectional"))
    )
    (net (code "35") (name "VCC") (class "Default")
      (node (ref "C11") (pin "2") (pinfunction "2_2") (pintype "passive"))
      (node (ref "C12") (pin "2") (pinfunction "2_2") (pintype "passive"))
      (node (ref "C13") (pin "2") (pinfunction "2_2") (pintype "passive"))
      (node (ref "C14") (pin "2") (pinfunction "2_2") (pintype "passive"))
      (node (ref "C17") (pin "2") (pinfunction "2_2") (pintype "passive"))
      (node (ref "C18") (pin "2") (pinfunction "2_2") (pintype "passive"))
      (node (ref "C19") (pin "2") (pinfunction "2_2") (pintype "passive"))
      (node (ref "C2") (pin "2") (pinfunction "2_2") (pintype "passive"))
      (node (ref "C23") (pin "1") (pinfunction "1_1") (pintype "passive"))
      (node (ref "C3") (pin "2") (pinfunction "2_2") (pintype "passive"))
      (node (ref "C6") (pin "2") (pinfunction "2_2") (pintype "passive"))
      (node (ref "C7") (pin "2") (pinfunction "2_2") (pintype "passive"))
      (node (ref "C8") (pin "2") (pinfunction "2_2") (pintype "passive"))
      (node (ref "IC2") (pin "1") (pinfunction "VIN_1") (pintype "input"))
      (node (ref "IC2") (pin "3") (pinfunction "CE_3") (pintype "input"))
      (node (ref "PL5") (pin "2") (pinfunction "S_2") (pintype "passive"))
      (node (ref "R17") (pin "1") (pinfunction "1_1") (pintype "passive"))
      (node (ref "U$2") (pin "7") (pinfunction "VIN_7") (pintype "passive"))
      (node (ref "U$3") (pin "7") (pinfunction "VIN_7") (pintype "passive"))
      (node (ref "U$4") (pin "7") (pinfunction "VIN_7") (pintype "passive"))
    )
    (net (code "36") (name "VOUT_6") (class "Default")
      (node (ref "C10") (pin "1") (pinfunction "+_1") (pintype "passive"))
      (node (ref "J6") (pin "1") (pinfunction "S_1") (pintype "passive"))
      (node (ref "J7") (pin "1") (pinfunction "S_1") (pintype "passive"))
      (node (ref "J8") (pin "1") (pinfunction "S_1") (pintype "passive"))
      (node (ref "J9") (pin "1") (pinfunction "S_1") (pintype "passive"))
      (node (ref "L2") (pin "2") (pinfunction "2_2") (pintype "passive"))
      (node (ref "R5") (pin "2") (pinfunction "2_2") (pintype "passive"))
      (node (ref "R7") (pin "2") (pinfunction "2_2") (pintype "passive"))
    )
    (net (code "37") (name "VOUT_MOTOR") (class "Default")
      (node (ref "C16") (pin "1") (pinfunction "+_1") (pintype "passive"))
      (node (ref "J1") (pin "2") (pinfunction "S_2") (pintype "passive"))
      (node (ref "J1") (pin "3") (pinfunction "S_3") (pintype "passive"))
      (node (ref "L3") (pin "2") (pinfunction "2_2") (pintype "passive"))
      (node (ref "R10") (pin "2") (pinfunction "2_2") (pintype "passive"))
      (node (ref "R8") (pin "2") (pinfunction "2_2") (pintype "passive"))
    )
    (net (code "38") (name "VPP{slash}MCLR") (class "Default")
      (node (ref "J11") (pin "7") (pinfunction "P$7_7") (pintype "power_in"))
      (node (ref "J11") (pin "8") (pinfunction "P$8_8") (pintype "power_in"))
      (node (ref "R14") (pin "2") (pinfunction "2_2") (pintype "passive"))
      (node (ref "U$6") (pin "4") (pinfunction "RA3/~{MCLR/VPP}_4") (pintype "bidirectional"))
    )
    (net (code "39") (name "unconnected-(IC2-CB-Pad4)") (class "Default")
      (node (ref "IC2") (pin "4") (pinfunction "CB_4") (pintype "input"))
    )
    (net (code "40") (name "unconnected-(U$1A-GPIO_8-PadP8.35)") (class "Default")
      (node (ref "U$1") (pin "P8.35") (pinfunction "GPIO_8_P8.35") (pintype "bidirectional"))
    )
    (net (code "41") (name "unconnected-(U$1A-GPIO_9-PadP8.33)") (class "Default")
      (node (ref "U$1") (pin "P8.33") (pinfunction "GPIO_9_P8.33") (pintype "bidirectional"))
    )
    (net (code "42") (name "unconnected-(U$1A-GPIO_10-PadP8.31)") (class "Default")
      (node (ref "U$1") (pin "P8.31") (pinfunction "GPIO_10_P8.31") (pintype "bidirectional"))
    )
    (net (code "43") (name "unconnected-(U$1A-GPIO_11-PadP8.32)") (class "Default")
      (node (ref "U$1") (pin "P8.32") (pinfunction "GPIO_11_P8.32") (pintype "bidirectional"))
    )
    (net (code "44") (name "unconnected-(U$1A-GPIO_22-PadP8.19)") (class "Default")
      (node (ref "U$1") (pin "P8.19") (pinfunction "GPIO_22_P8.19") (pintype "bidirectional"))
    )
    (net (code "45") (name "unconnected-(U$1A-GPIO_23-PadP8.13)") (class "Default")
      (node (ref "U$1") (pin "P8.13") (pinfunction "GPIO_23_P8.13") (pintype "bidirectional"))
    )
    (net (code "46") (name "unconnected-(U$1A-GPIO_26-PadP8.14)") (class "Default")
      (node (ref "U$1") (pin "P8.14") (pinfunction "GPIO_26_P8.14") (pintype "bidirectional"))
    )
    (net (code "47") (name "unconnected-(U$1A-GPIO_27-PadP8.17)") (class "Default")
      (node (ref "U$1") (pin "P8.17") (pinfunction "GPIO_27_P8.17") (pintype "bidirectional"))
    )
    (net (code "48") (name "unconnected-(U$1A-GPIO_32-PadP8.25)") (class "Default")
      (node (ref "U$1") (pin "P8.25") (pinfunction "GPIO_32_P8.25") (pintype "bidirectional"))
    )
    (net (code "49") (name "unconnected-(U$1A-GPIO_33-PadP8.24)") (class "Default")
      (node (ref "U$1") (pin "P8.24") (pinfunction "GPIO_33_P8.24") (pintype "bidirectional"))
    )
    (net (code "50") (name "unconnected-(U$1A-GPIO_34-PadP8.5)") (class "Default")
      (node (ref "U$1") (pin "P8.5") (pinfunction "GPIO_34_P8.5") (pintype "bidirectional"))
    )
    (net (code "51") (name "unconnected-(U$1A-GPIO_35-PadP8.6)") (class "Default")
      (node (ref "U$1") (pin "P8.6") (pinfunction "GPIO_35_P8.6") (pintype "bidirectional"))
    )
    (net (code "52") (name "unconnected-(U$1A-GPIO_36-PadP8.23)") (class "Default")
      (node (ref "U$1") (pin "P8.23") (pinfunction "GPIO_36_P8.23") (pintype "bidirectional"))
    )
    (net (code "53") (name "unconnected-(U$1A-GPIO_37-PadP8.22)") (class "Default")
      (node (ref "U$1") (pin "P8.22") (pinfunction "GPIO_37_P8.22") (pintype "bidirectional"))
    )
    (net (code "54") (name "unconnected-(U$1A-GPIO_38-PadP8.3)") (class "Default")
      (node (ref "U$1") (pin "P8.3") (pinfunction "GPIO_38_P8.3") (pintype "bidirectional"))
    )
    (net (code "55") (name "unconnected-(U$1A-GPIO_39-PadP8.4)") (class "Default")
      (node (ref "U$1") (pin "P8.4") (pinfunction "GPIO_39_P8.4") (pintype "bidirectional"))
    )
    (net (code "56") (name "unconnected-(U$1A-GPIO_44-PadP8.12)") (class "Default")
      (node (ref "U$1") (pin "P8.12") (pinfunction "GPIO_44_P8.12") (pintype "bidirectional"))
    )
    (net (code "57") (name "unconnected-(U$1A-GPIO_45-PadP8.11)") (class "Default")
      (node (ref "U$1") (pin "P8.11") (pinfunction "GPIO_45_P8.11") (pintype "bidirectional"))
    )
    (net (code "58") (name "unconnected-(U$1A-GPIO_46-PadP8.16)") (class "Default")
      (node (ref "U$1") (pin "P8.16") (pinfunction "GPIO_46_P8.16") (pintype "bidirectional"))
    )
    (net (code "59") (name "unconnected-(U$1A-GPIO_47-PadP8.15)") (class "Default")
      (node (ref "U$1") (pin "P8.15") (pinfunction "GPIO_47_P8.15") (pintype "bidirectional"))
    )
    (net (code "60") (name "unconnected-(U$1A-GPIO_61-PadP8.26)") (class "Default")
      (node (ref "U$1") (pin "P8.26") (pinfunction "GPIO_61_P8.26") (pintype "bidirectional"))
    )
    (net (code "61") (name "unconnected-(U$1A-GPIO_62-PadP8.21)") (class "Default")
      (node (ref "U$1") (pin "P8.21") (pinfunction "GPIO_62_P8.21") (pintype "bidirectional"))
    )
    (net (code "62") (name "unconnected-(U$1A-GPIO_63-PadP8.20)") (class "Default")
      (node (ref "U$1") (pin "P8.20") (pinfunction "GPIO_63_P8.20") (pintype "bidirectional"))
    )
    (net (code "63") (name "unconnected-(U$1A-GPIO_65-PadP8.18)") (class "Default")
      (node (ref "U$1") (pin "P8.18") (pinfunction "GPIO_65_P8.18") (pintype "bidirectional"))
    )
    (net (code "64") (name "unconnected-(U$1A-GPIO_68-PadP8.10)") (class "Default")
      (node (ref "U$1") (pin "P8.10") (pinfunction "GPIO_68_P8.10") (pintype "bidirectional"))
    )
    (net (code "65") (name "unconnected-(U$1A-GPIO_69-PadP8.9)") (class "Default")
      (node (ref "U$1") (pin "P8.9") (pinfunction "GPIO_69_P8.9") (pintype "bidirectional"))
    )
    (net (code "66") (name "unconnected-(U$1A-GPIO_70-PadP8.45)") (class "Default")
      (node (ref "U$1") (pin "P8.45") (pinfunction "GPIO_70_P8.45") (pintype "bidirectional"))
    )
    (net (code "67") (name "unconnected-(U$1A-GPIO_71-PadP8.46)") (class "Default")
      (node (ref "U$1") (pin "P8.46") (pinfunction "GPIO_71_P8.46") (pintype "bidirectional"))
    )
    (net (code "68") (name "unconnected-(U$1A-GPIO_72-PadP8.43)") (class "Default")
      (node (ref "U$1") (pin "P8.43") (pinfunction "GPIO_72_P8.43") (pintype "bidirectional"))
    )
    (net (code "69") (name "unconnected-(U$1A-GPIO_73-PadP8.44)") (class "Default")
      (node (ref "U$1") (pin "P8.44") (pinfunction "GPIO_73_P8.44") (pintype "bidirectional"))
    )
    (net (code "70") (name "unconnected-(U$1A-GPIO_74-PadP8.41)") (class "Default")
      (node (ref "U$1") (pin "P8.41") (pinfunction "GPIO_74_P8.41") (pintype "bidirectional"))
    )
    (net (code "71") (name "unconnected-(U$1A-GPIO_75-PadP8.42)") (class "Default")
      (node (ref "U$1") (pin "P8.42") (pinfunction "GPIO_75_P8.42") (pintype "bidirectional"))
    )
    (net (code "72") (name "unconnected-(U$1A-GPIO_76-PadP8.39)") (class "Default")
      (node (ref "U$1") (pin "P8.39") (pinfunction "GPIO_76_P8.39") (pintype "bidirectional"))
    )
    (net (code "73") (name "unconnected-(U$1A-GPIO_77-PadP8.40)") (class "Default")
      (node (ref "U$1") (pin "P8.40") (pinfunction "GPIO_77_P8.40") (pintype "bidirectional"))
    )
    (net (code "74") (name "unconnected-(U$1A-GPIO_78-PadP8.37)") (class "Default")
      (node (ref "U$1") (pin "P8.37") (pinfunction "GPIO_78_P8.37") (pintype "bidirectional"))
    )
    (net (code "75") (name "unconnected-(U$1A-GPIO_79-PadP8.38)") (class "Default")
      (node (ref "U$1") (pin "P8.38") (pinfunction "GPIO_79_P8.38") (pintype "bidirectional"))
    )
    (net (code "76") (name "unconnected-(U$1A-GPIO_80-PadP8.36)") (class "Default")
      (node (ref "U$1") (pin "P8.36") (pinfunction "GPIO_80_P8.36") (pintype "bidirectional"))
    )
    (net (code "77") (name "unconnected-(U$1A-GPIO_81-PadP8.34)") (class "Default")
      (node (ref "U$1") (pin "P8.34") (pinfunction "GPIO_81_P8.34") (pintype "bidirectional"))
    )
    (net (code "78") (name "unconnected-(U$1A-GPIO_86-PadP8.27)") (class "Default")
      (node (ref "U$1") (pin "P8.27") (pinfunction "GPIO_86_P8.27") (pintype "bidirectional"))
    )
    (net (code "79") (name "unconnected-(U$1A-GPIO_87-PadP8.29)") (class "Default")
      (node (ref "U$1") (pin "P8.29") (pinfunction "GPIO_87_P8.29") (pintype "bidirectional"))
    )
    (net (code "80") (name "unconnected-(U$1A-GPIO_88-PadP8.28)") (class "Default")
      (node (ref "U$1") (pin "P8.28") (pinfunction "GPIO_88_P8.28") (pintype "bidirectional"))
    )
    (net (code "81") (name "unconnected-(U$1A-GPIO_89-PadP8.30)") (class "Default")
      (node (ref "U$1") (pin "P8.30") (pinfunction "GPIO_89_P8.30") (pintype "bidirectional"))
    )
    (net (code "82") (name "unconnected-(U$1B-AIN0-PadP9.39)") (class "Default")
      (node (ref "U$1") (pin "P9.39") (pinfunction "AIN0_P9.39") (pintype "bidirectional"))
    )
    (net (code "83") (name "unconnected-(U$1B-AIN1-PadP9.40)") (class "Default")
      (node (ref "U$1") (pin "P9.40") (pinfunction "AIN1_P9.40") (pintype "bidirectional"))
    )
    (net (code "84") (name "unconnected-(U$1B-AIN2-PadP9.37)") (class "Default")
      (node (ref "U$1") (pin "P9.37") (pinfunction "AIN2_P9.37") (pintype "bidirectional"))
    )
    (net (code "85") (name "unconnected-(U$1B-AIN3-PadP9.38)") (class "Default")
      (node (ref "U$1") (pin "P9.38") (pinfunction "AIN3_P9.38") (pintype "bidirectional"))
    )
    (net (code "86") (name "unconnected-(U$1B-AIN4-PadP9.33)") (class "Default")
      (node (ref "U$1") (pin "P9.33") (pinfunction "AIN4_P9.33") (pintype "bidirectional"))
    )
    (net (code "87") (name "unconnected-(U$1B-AIN5-PadP9.36)") (class "Default")
      (node (ref "U$1") (pin "P9.36") (pinfunction "AIN5_P9.36") (pintype "bidirectional"))
    )
    (net (code "88") (name "unconnected-(U$1B-AIN6-PadP9.35)") (class "Default")
      (node (ref "U$1") (pin "P9.35") (pinfunction "AIN6_P9.35") (pintype "bidirectional"))
    )
    (net (code "89") (name "unconnected-(U$1B-GNDA_ADC-PadP9.34)") (class "Default")
      (node (ref "U$1") (pin "P9.34") (pinfunction "GNDA_ADC_P9.34") (pintype "bidirectional"))
    )
    (net (code "90") (name "unconnected-(U$1B-GPIO_2-PadP9.22)") (class "Default")
      (node (ref "U$1") (pin "P9.22") (pinfunction "GPIO_2_P9.22") (pintype "bidirectional"))
    )
    (net (code "91") (name "unconnected-(U$1B-GPIO_3-PadP9.21)") (class "Default")
      (node (ref "U$1") (pin "P9.21") (pinfunction "GPIO_3_P9.21") (pintype "bidirectional"))
    )
    (net (code "92") (name "unconnected-(U$1B-GPIO_4-PadP9.17)") (class "Default")
      (node (ref "U$1") (pin "P9.17") (pinfunction "GPIO_4_P9.17") (pintype "bidirectional"))
    )
    (net (code "93") (name "unconnected-(U$1B-GPIO_5-PadP9.18)") (class "Default")
      (node (ref "U$1") (pin "P9.18") (pinfunction "GPIO_5_P9.18") (pintype "bidirectional"))
    )
    (net (code "94") (name "unconnected-(U$1B-GPIO_7-PadP9.42)") (class "Default")
      (node (ref "U$1") (pin "P9.42") (pinfunction "GPIO_7_P9.42") (pintype "bidirectional"))
    )
    (net (code "95") (name "unconnected-(U$1B-GPIO_14-PadP9.26)") (class "Default")
      (node (ref "U$1") (pin "P9.26") (pinfunction "GPIO_14_P9.26") (pintype "bidirectional"))
    )
    (net (code "96") (name "unconnected-(U$1B-GPIO_15-PadP9.24)") (class "Default")
      (node (ref "U$1") (pin "P9.24") (pinfunction "GPIO_15_P9.24") (pintype "bidirectional"))
    )
    (net (code "97") (name "unconnected-(U$1B-GPIO_20-PadP9.41)") (class "Default")
      (node (ref "U$1") (pin "P9.41") (pinfunction "GPIO_20_P9.41") (pintype "bidirectional"))
    )
    (net (code "98") (name "unconnected-(U$1B-GPIO_30-PadP9.11)") (class "Default")
      (node (ref "U$1") (pin "P9.11") (pinfunction "GPIO_30_P9.11") (pintype "bidirectional"))
    )
    (net (code "99") (name "unconnected-(U$1B-GPIO_31-PadP9.13)") (class "Default")
      (node (ref "U$1") (pin "P9.13") (pinfunction "GPIO_31_P9.13") (pintype "bidirectional"))
    )
    (net (code "100") (name "unconnected-(U$1B-GPIO_40-PadP9.14)") (class "Default")
      (node (ref "U$1") (pin "P9.14") (pinfunction "GPIO_40_P9.14") (pintype "bidirectional"))
    )
    (net (code "101") (name "unconnected-(U$1B-GPIO_48-PadP9.15)") (class "Default")
      (node (ref "U$1") (pin "P9.15") (pinfunction "GPIO_48_P9.15") (pintype "bidirectional"))
    )
    (net (code "102") (name "unconnected-(U$1B-GPIO_49-PadP9.23)") (class "Default")
      (node (ref "U$1") (pin "P9.23") (pinfunction "GPIO_49_P9.23") (pintype "bidirectional"))
    )
    (net (code "103") (name "unconnected-(U$1B-GPIO_51-PadP9.16)") (class "Default")
      (node (ref "U$1") (pin "P9.16") (pinfunction "GPIO_51_P9.16") (pintype "bidirectional"))
    )
    (net (code "104") (name "unconnected-(U$1B-GPIO_60-PadP9.12)") (class "Default")
      (node (ref "U$1") (pin "P9.12") (pinfunction "GPIO_60_P9.12") (pintype "bidirectional"))
    )
    (net (code "105") (name "unconnected-(U$1B-GPIO_117-PadP9.25)") (class "Default")
      (node (ref "U$1") (pin "P9.25") (pinfunction "GPIO_117_P9.25") (pintype "bidirectional"))
    )
    (net (code "106") (name "unconnected-(U$1B-GPIO_120-PadP9.31)") (class "Default")
      (node (ref "U$1") (pin "P9.31") (pinfunction "GPIO_120_P9.31") (pintype "bidirectional"))
    )
    (net (code "107") (name "unconnected-(U$1B-GPIO_121-PadP9.29)") (class "Default")
      (node (ref "U$1") (pin "P9.29") (pinfunction "GPIO_121_P9.29") (pintype "bidirectional"))
    )
    (net (code "108") (name "unconnected-(U$1B-GPIO_122-PadP9.30)") (class "Default")
      (node (ref "U$1") (pin "P9.30") (pinfunction "GPIO_122_P9.30") (pintype "bidirectional"))
    )
    (net (code "109") (name "unconnected-(U$1B-GPIO_123-PadP9.28)") (class "Default")
      (node (ref "U$1") (pin "P9.28") (pinfunction "GPIO_123_P9.28") (pintype "bidirectional"))
    )
    (net (code "110") (name "unconnected-(U$1B-GPIO_125-PadP9.27)") (class "Default")
      (node (ref "U$1") (pin "P9.27") (pinfunction "GPIO_125_P9.27") (pintype "bidirectional"))
    )
    (net (code "111") (name "unconnected-(U$1B-I2C2_SCL-PadP9.19)") (class "Default")
      (node (ref "U$1") (pin "P9.19") (pinfunction "I2C2_SCL_P9.19") (pintype "bidirectional"))
    )
    (net (code "112") (name "unconnected-(U$1B-I2C2_SDA-PadP9.20)") (class "Default")
      (node (ref "U$1") (pin "P9.20") (pinfunction "I2C2_SDA_P9.20") (pintype "bidirectional"))
    )
    (net (code "113") (name "unconnected-(U$1B-SYS_5V-PadP9.7)") (class "Default")
      (node (ref "U$1") (pin "P9.7") (pinfunction "SYS_5V_P9.7") (pintype "bidirectional"))
    )
    (net (code "114") (name "unconnected-(U$1B-SYS_5V-PadP9.8)") (class "Default")
      (node (ref "U$1") (pin "P9.8") (pinfunction "SYS_5V_P9.8") (pintype "bidirectional"))
    )
    (net (code "115") (name "unconnected-(U$1B-SYS_RESET~{N}-PadP9.10)") (class "Default")
      (node (ref "U$1") (pin "P9.10") (pinfunction "SYS_RESET~{N}_P9.10") (pintype "bidirectional"))
    )
    (net (code "116") (name "unconnected-(U$1B-VDD_3V3-PadP9.3)") (class "Default")
      (node (ref "U$1") (pin "P9.3") (pinfunction "VDD_3V3_P9.3") (pintype "bidirectional"))
    )
    (net (code "117") (name "unconnected-(U$1B-VDD_3V3-PadP9.4)") (class "Default")
      (node (ref "U$1") (pin "P9.4") (pinfunction "VDD_3V3_P9.4") (pintype "bidirectional"))
    )
    (net (code "118") (name "unconnected-(U$1B-VDD_ADC-PadP9.32)") (class "Default")
      (node (ref "U$1") (pin "P9.32") (pinfunction "VDD_ADC_P9.32") (pintype "bidirectional"))
    )
    (net (code "119") (name "unconnected-(U$6-RC2{slash}AN6-Pad8)") (class "Default")
      (node (ref "U$6") (pin "8") (pinfunction "RC2/AN6_8") (pintype "bidirectional"))
    )
  )
)
